# motorController.net
KiCad netlist of a schematic drawn in EAGLE
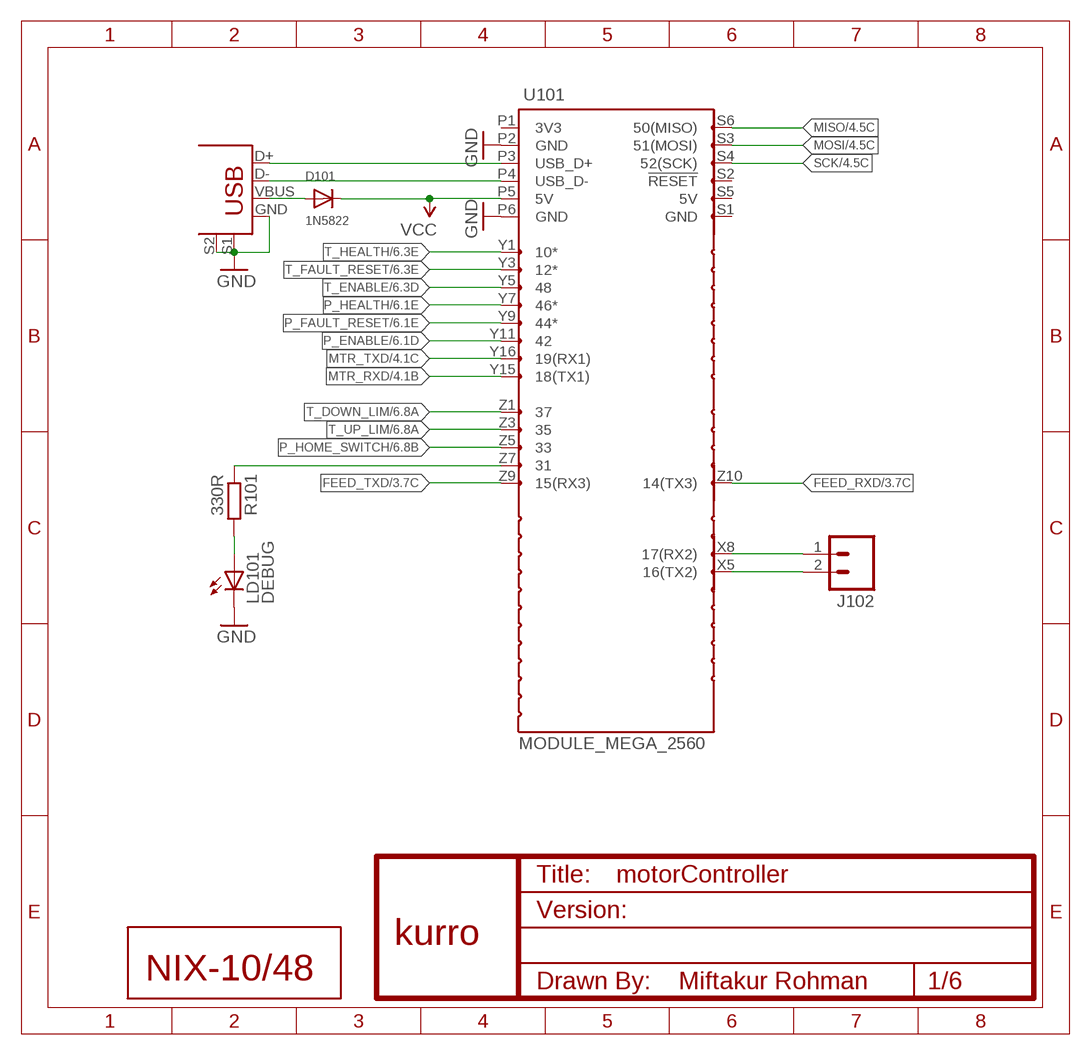
[diagram p0: schematic, sheet 1]
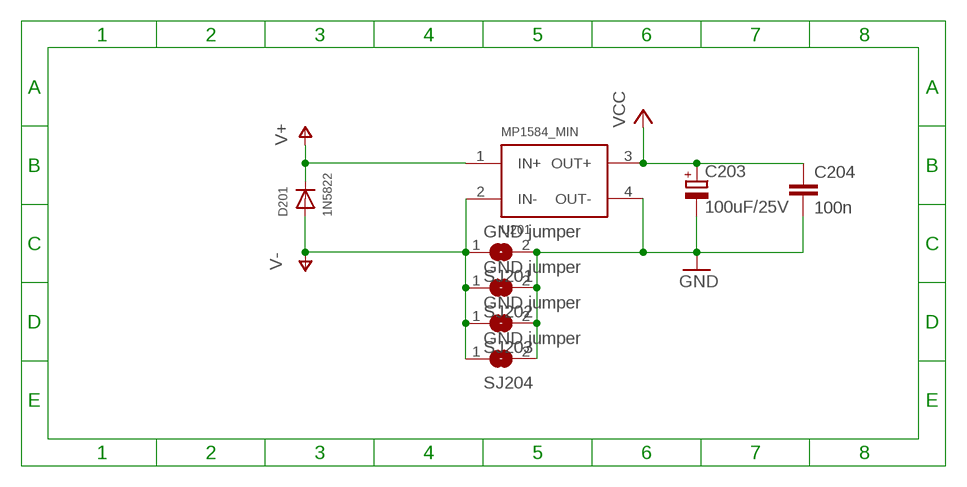
[diagram p1: schematic, sheet 2]
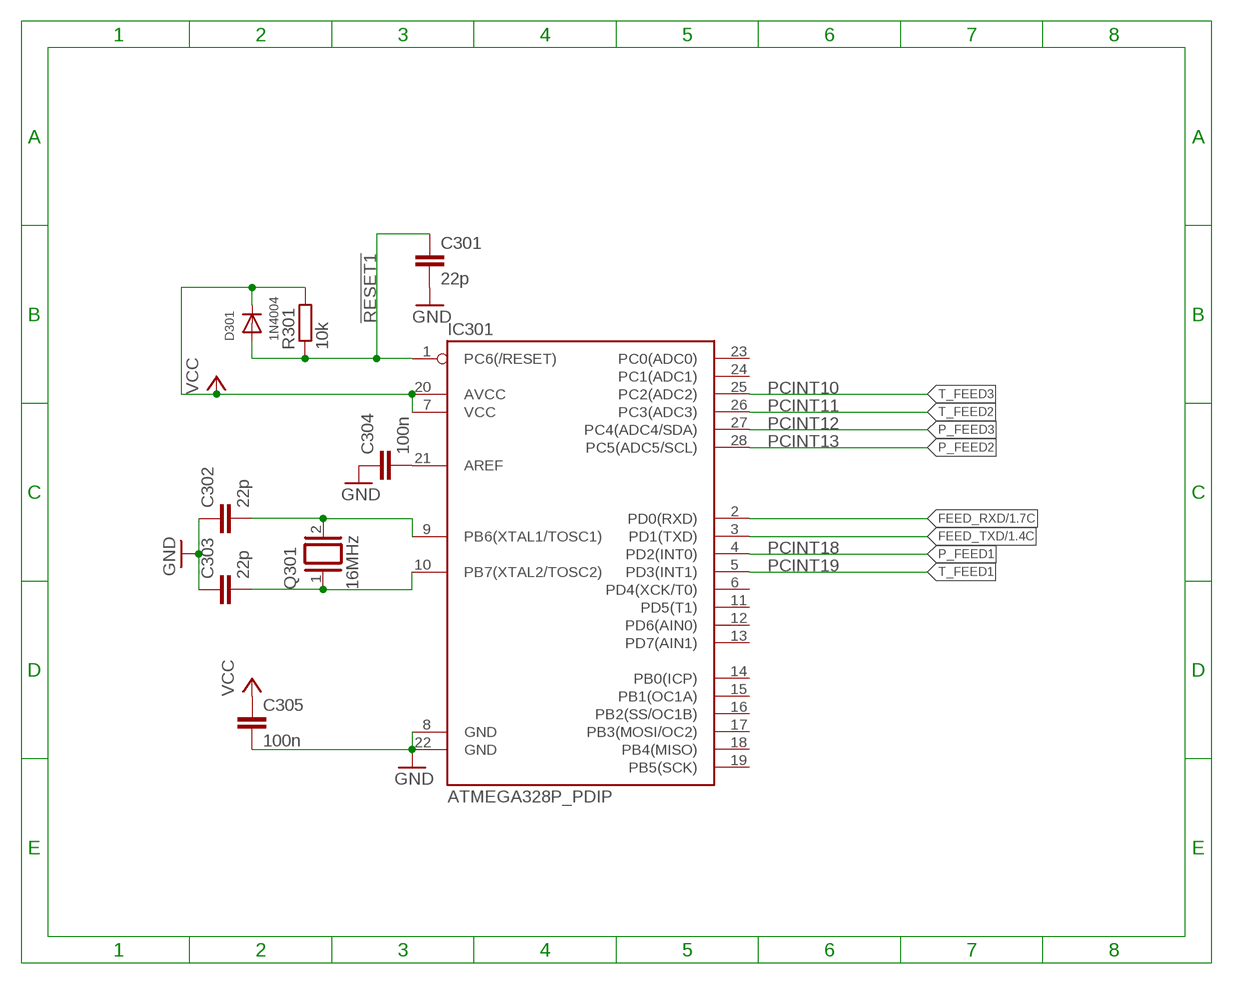
[diagram p2: schematic, sheet 3]
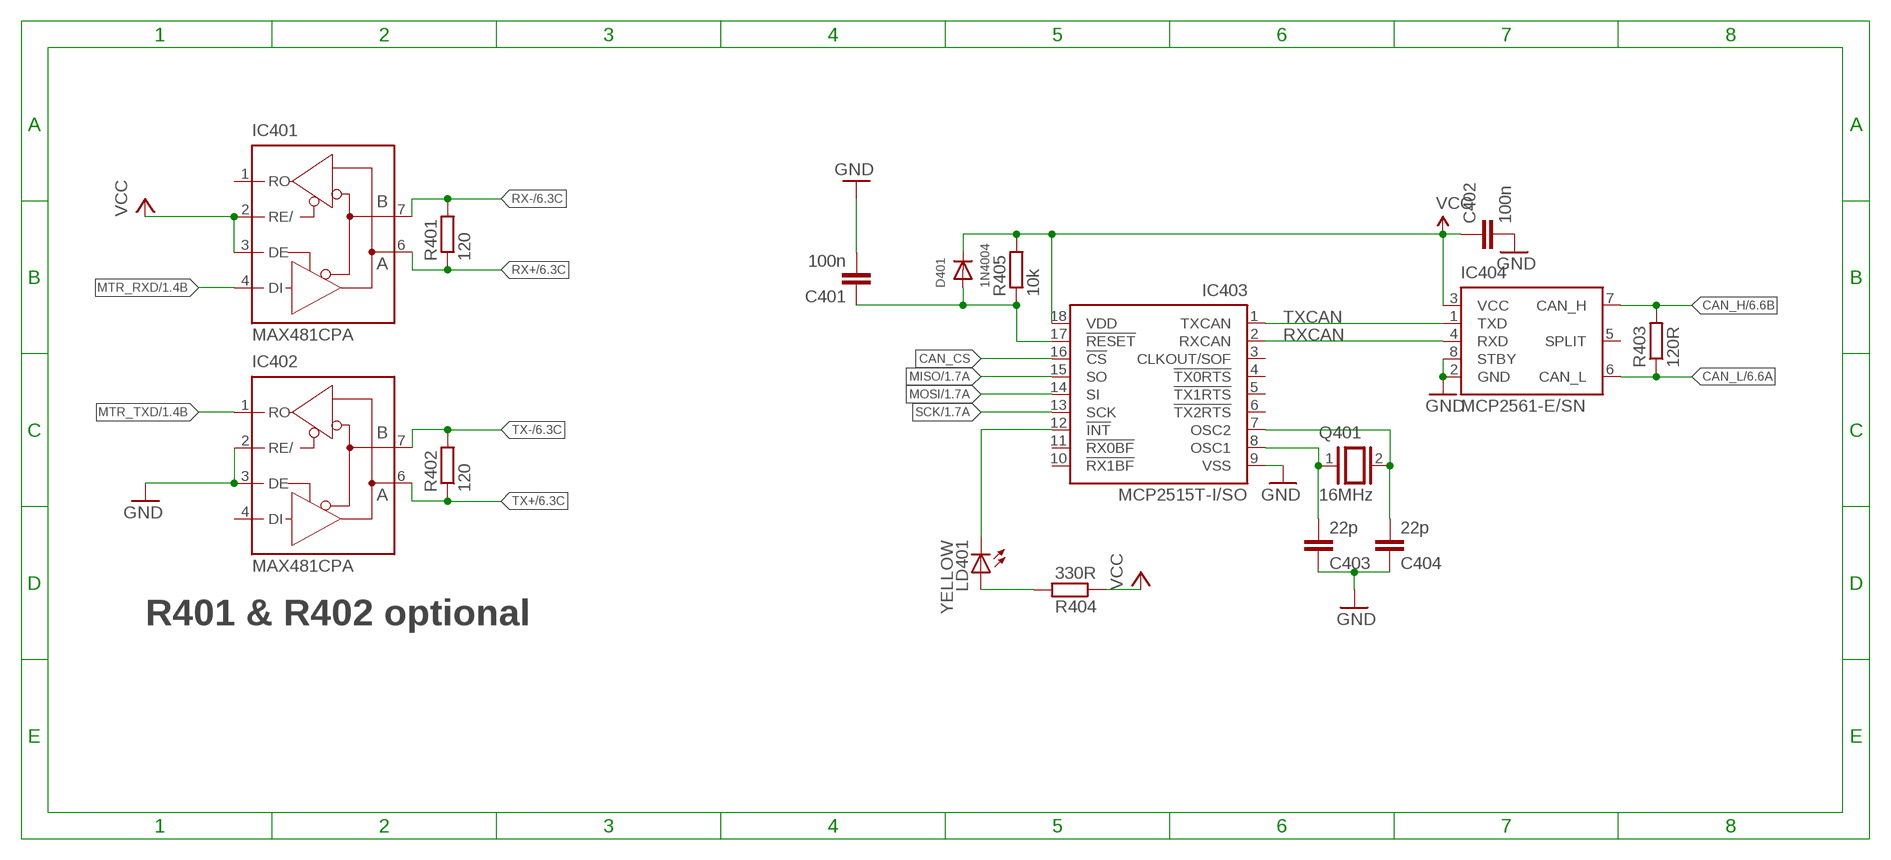
[diagram p3: schematic, sheet 4]
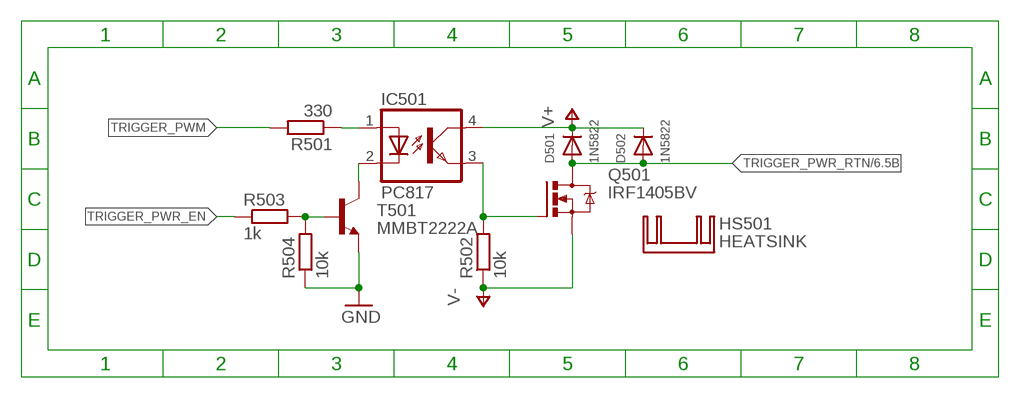
[diagram p4: schematic, sheet 5]
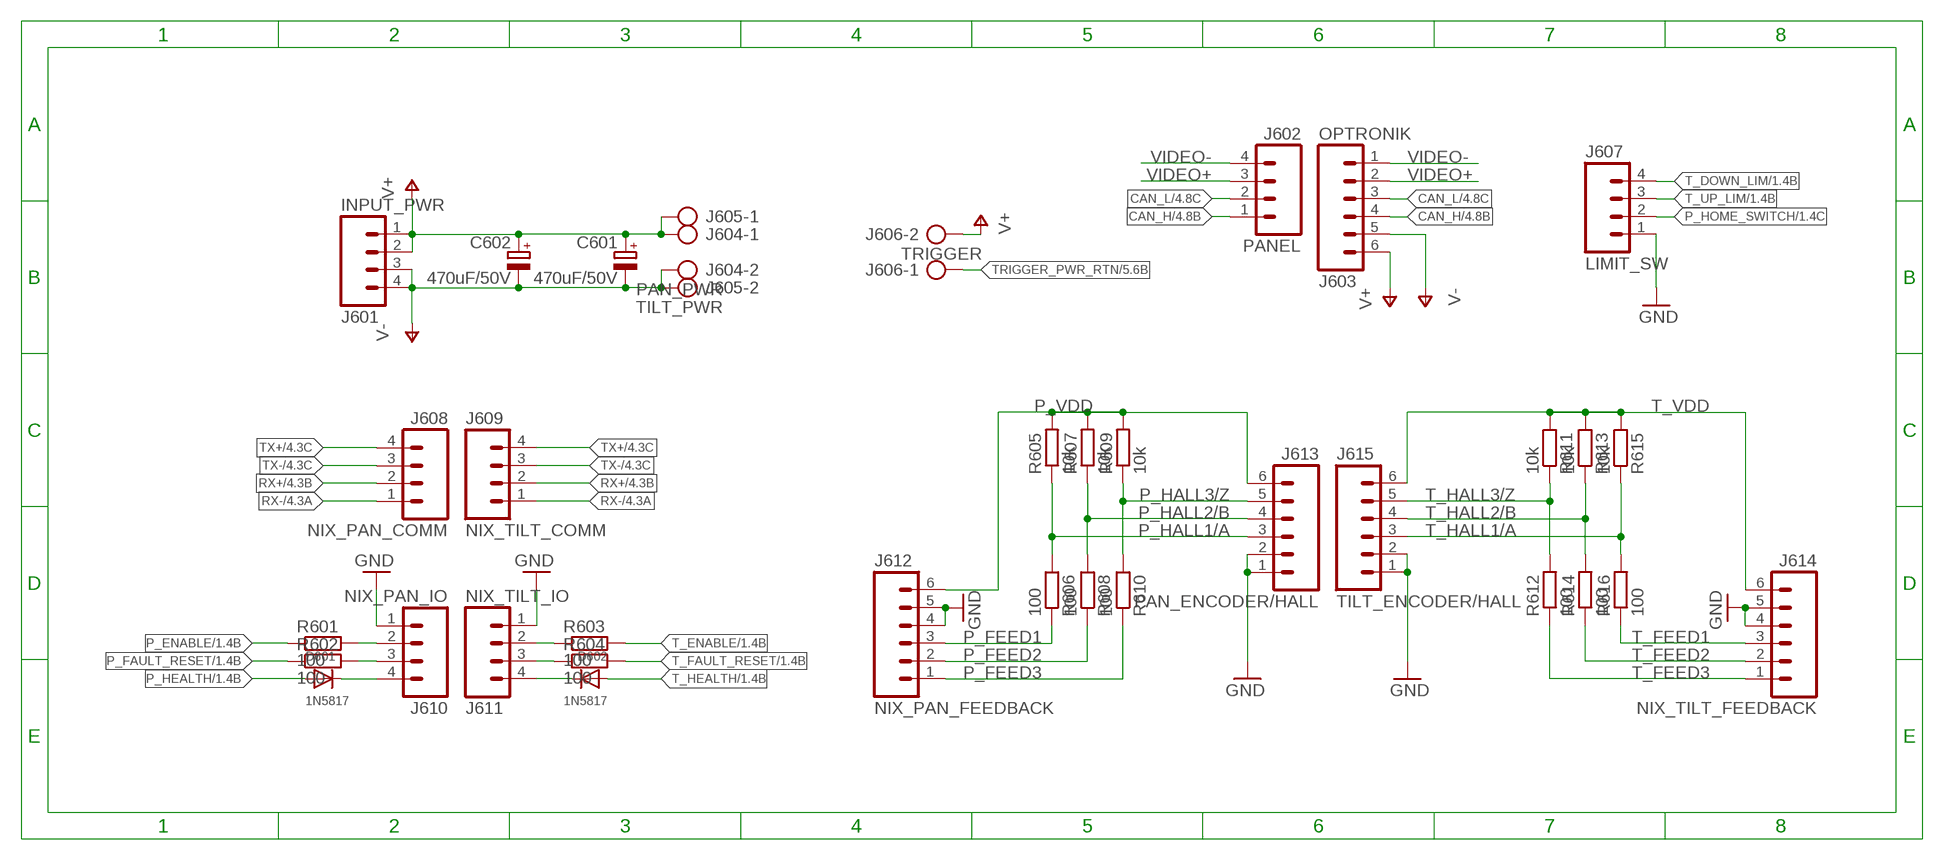
[diagram p5: schematic, sheet 6]

(export (version "E")
  (design (tool "Eeschema 10.0.6"))
  (components
    (comp (ref "D501")
      (value "1N5822")
      (footprint "eagle-import:SMADIODE")
      (libsource (lib "eagle-import") (part "DIODESMA"))
    )
    (comp (ref "D502")
      (value "1N5822")
      (footprint "eagle-import:SMADIODE")
      (libsource (lib "eagle-import") (part "DIODESMA"))
    )
    (comp (ref "HS501")
      (value "HEATSINK")
      (footprint "eagle-import:BV_150X105")
      (libsource (lib "eagle-import") (part "TO220T30"))
    )
    (comp (ref "IC501")
      (value "PC817")
      (footprint "eagle-import:DIL04")
      (libsource (lib "eagle-import") (part "PC817"))
    )
    (comp (ref "Q501")
      (value "IRF1405BV")
      (footprint "eagle-import:TO220BV")
      (libsource (lib "eagle-import") (part "IRF1405BV"))
    )
    (comp (ref "R501")
      (value "330")
      (footprint "eagle-import:R0603")
      (libsource (lib "eagle-import") (part "resistor_R-EU_R0603"))
    )
    (comp (ref "R502")
      (value "10k")
      (footprint "eagle-import:R0603")
      (libsource (lib "eagle-import") (part "resistor_R-EU_R0603"))
    )
    (comp (ref "R503")
      (value "1k")
      (footprint "eagle-import:R0603")
      (libsource (lib "eagle-import") (part "resistor_R-EU_R0603"))
    )
    (comp (ref "R504")
      (value "10k")
      (footprint "eagle-import:R0603")
      (libsource (lib "eagle-import") (part "resistor_R-EU_R0603"))
    )
    (comp (ref "T501")
      (value "MMBT2222A")
      (footprint "eagle-import:SOT23")
      (libsource (lib "eagle-import") (part "TRANSISTOR_NPNSOT23"))
    )
    (comp (ref "C203")
      (value "100uF/25V")
      (footprint "eagle-import:E5-10,5")
      (libsource (lib "eagle-import") (part "CPOL-EUE5-10.5"))
    )
    (comp (ref "C204")
      (value "100n")
      (footprint "eagle-import:C0603")
      (libsource (lib "eagle-import") (part "resistor_C-EUC0603"))
    )
    (comp (ref "D201")
      (value "1N5822")
      (footprint "eagle-import:SMADIODE")
      (libsource (lib "eagle-import") (part "DIODESMA"))
    )
    (comp (ref "SJ201")
      (value "GND jumper")
      (footprint "eagle-import:SJS")
      (libsource (lib "eagle-import") (part "SJS"))
    )
    (comp (ref "SJ202")
      (value "GND jumper")
      (footprint "eagle-import:SJS")
      (libsource (lib "eagle-import") (part "SJS"))
    )
    (comp (ref "SJ203")
      (value "GND jumper")
      (footprint "eagle-import:SJS")
      (libsource (lib "eagle-import") (part "SJS"))
    )
    (comp (ref "SJ204")
      (value "GND jumper")
      (footprint "eagle-import:SJS")
      (libsource (lib "eagle-import") (part "SJS"))
    )
    (comp (ref "U201")
      (value "MP1584_MIN")
      (footprint "eagle-import:MP1584_MIN")
      (libsource (lib "eagle-import") (part "MP1584_MIN"))
    )
    (comp (ref "C601")
      (value "470uF/50V")
      (footprint "eagle-import:E5-10,5")
      (libsource (lib "eagle-import") (part "CPOL-EUE5-10.5"))
    )
    (comp (ref "C602")
      (value "470uF/50V")
      (footprint "eagle-import:E5-10,5")
      (libsource (lib "eagle-import") (part "CPOL-EUE5-10.5"))
    )
    (comp (ref "D601")
      (value "1N5817")
      (footprint "eagle-import:SOD-323F")
      (libsource (lib "eagle-import") (part "DIODESOD-323F"))
    )
    (comp (ref "D602")
      (value "1N5817")
      (footprint "eagle-import:SOD-323F")
      (libsource (lib "eagle-import") (part "DIODESOD-323F"))
    )
    (comp (ref "J601")
      (value "INPUT_PWR")
      (footprint "eagle-import:XH-4-RA")
      (libsource (lib "eagle-import") (part "M04-XH-RA"))
    )
    (comp (ref "J602")
      (value "PANEL")
      (footprint "eagle-import:XH-4-RA")
      (libsource (lib "eagle-import") (part "M04-XH-RA"))
    )
    (comp (ref "J603")
      (value "OPTRONIK")
      (footprint "eagle-import:XH-6-RA")
      (libsource (lib "eagle-import") (part "M06-XH-RA"))
    )
    (comp (ref "J604")
      (value "PAN_PWR")
      (footprint "eagle-import:AK200_2")
      (libsource (lib "eagle-import") (part "AK200/2"))
    )
    (comp (ref "J605")
      (value "TILT_PWR")
      (footprint "eagle-import:AK200_2")
      (libsource (lib "eagle-import") (part "AK200/2"))
    )
    (comp (ref "J606")
      (value "TRIGGER")
      (footprint "eagle-import:AK200_2")
      (libsource (lib "eagle-import") (part "AK200/2"))
    )
    (comp (ref "J607")
      (value "LIMIT_SW")
      (footprint "eagle-import:XH-4-RA")
      (libsource (lib "eagle-import") (part "M04-XH-RA"))
    )
    (comp (ref "J608")
      (value "NIX_PAN_COMM")
      (footprint "eagle-import:XH-4-RA")
      (libsource (lib "eagle-import") (part "M04-XH-RA"))
    )
    (comp (ref "J609")
      (value "NIX_TILT_COMM")
      (footprint "eagle-import:XH-4-RA")
      (libsource (lib "eagle-import") (part "M04-XH-RA"))
    )
    (comp (ref "J610")
      (value "NIX_PAN_IO")
      (footprint "eagle-import:XH-4-RA")
      (libsource (lib "eagle-import") (part "M04-XH-RA"))
    )
    (comp (ref "J611")
      (value "NIX_TILT_IO")
      (footprint "eagle-import:XH-4-RA")
      (libsource (lib "eagle-import") (part "M04-XH-RA"))
    )
    (comp (ref "J612")
      (value "NIX_PAN_FEEDBACK")
      (footprint "eagle-import:XH-6-RA")
      (libsource (lib "eagle-import") (part "M06-XH-RA"))
    )
    (comp (ref "J613")
      (value "PAN_ENCODER/HALL")
      (footprint "eagle-import:MOLEX-1X6")
      (libsource (lib "eagle-import") (part "M06POLAR"))
    )
    (comp (ref "J614")
      (value "NIX_TILT_FEEDBACK")
      (footprint "eagle-import:XH-6-RA")
      (libsource (lib "eagle-import") (part "M06-XH-RA"))
    )
    (comp (ref "J615")
      (value "TILT_ENCODER/HALL")
      (footprint "eagle-import:MOLEX-1X6")
      (libsource (lib "eagle-import") (part "M06POLAR"))
    )
    (comp (ref "R601")
      (value "100")
      (footprint "eagle-import:R0603")
      (libsource (lib "eagle-import") (part "R-EU_R0603"))
    )
    (comp (ref "R602")
      (value "100")
      (footprint "eagle-import:R0603")
      (libsource (lib "eagle-import") (part "R-EU_R0603"))
    )
    (comp (ref "R603")
      (value "100")
      (footprint "eagle-import:R0603")
      (libsource (lib "eagle-import") (part "R-EU_R0603"))
    )
    (comp (ref "R604")
      (value "100")
      (footprint "eagle-import:R0603")
      (libsource (lib "eagle-import") (part "R-EU_R0603"))
    )
    (comp (ref "R605")
      (value "10k")
      (footprint "eagle-import:R0603")
      (libsource (lib "eagle-import") (part "R-EU_R0603"))
    )
    (comp (ref "R606")
      (value "100")
      (footprint "eagle-import:R0603")
      (libsource (lib "eagle-import") (part "R-EU_R0603"))
    )
    (comp (ref "R607")
      (value "10k")
      (footprint "eagle-import:R0603")
      (libsource (lib "eagle-import") (part "R-EU_R0603"))
    )
    (comp (ref "R608")
      (value "100")
      (footprint "eagle-import:R0603")
      (libsource (lib "eagle-import") (part "R-EU_R0603"))
    )
    (comp (ref "R609")
      (value "10k")
      (footprint "eagle-import:R0603")
      (libsource (lib "eagle-import") (part "R-EU_R0603"))
    )
    (comp (ref "R610")
      (value "100")
      (footprint "eagle-import:R0603")
      (libsource (lib "eagle-import") (part "R-EU_R0603"))
    )
    (comp (ref "R611")
      (value "10k")
      (footprint "eagle-import:R0603")
      (libsource (lib "eagle-import") (part "R-EU_R0603"))
    )
    (comp (ref "R612")
      (value "100")
      (footprint "eagle-import:R0603")
      (libsource (lib "eagle-import") (part "R-EU_R0603"))
    )
    (comp (ref "R613")
      (value "10k")
      (footprint "eagle-import:R0603")
      (libsource (lib "eagle-import") (part "R-EU_R0603"))
    )
    (comp (ref "R614")
      (value "100")
      (footprint "eagle-import:R0603")
      (libsource (lib "eagle-import") (part "R-EU_R0603"))
    )
    (comp (ref "R615")
      (value "10k")
      (footprint "eagle-import:R0603")
      (libsource (lib "eagle-import") (part "R-EU_R0603"))
    )
    (comp (ref "R616")
      (value "100")
      (footprint "eagle-import:R0603")
      (libsource (lib "eagle-import") (part "R-EU_R0603"))
    )
    (comp (ref "C401")
      (value "100n")
      (footprint "eagle-import:C0603")
      (libsource (lib "eagle-import") (part "C-EUC0603"))
    )
    (comp (ref "C402")
      (value "100n")
      (footprint "eagle-import:C0603")
      (libsource (lib "eagle-import") (part "C-EUC0603"))
    )
    (comp (ref "C403")
      (value "22p")
      (footprint "eagle-import:C0603")
      (libsource (lib "eagle-import") (part "C-EUC0603"))
    )
    (comp (ref "C404")
      (value "22p")
      (footprint "eagle-import:C0603")
      (libsource (lib "eagle-import") (part "C-EUC0603"))
    )
    (comp (ref "D401")
      (value "1N4004")
      (footprint "eagle-import:SOD-323F")
      (libsource (lib "eagle-import") (part "DIODESOD-323F"))
    )
    (comp (ref "IC401")
      (value "MAX481CPA")
      (footprint "eagle-import:DIL08")
      (libsource (lib "eagle-import") (part "MAX481CPA"))
    )
    (comp (ref "IC402")
      (value "MAX481CPA")
      (footprint "eagle-import:DIL08")
      (libsource (lib "eagle-import") (part "MAX481CPA"))
    )
    (comp (ref "IC403")
      (value "MCP2515T-I/SO")
      (footprint "eagle-import:SO-18")
      (libsource (lib "eagle-import") (part "MCP2515T-I/SO"))
    )
    (comp (ref "IC404")
      (value "MCP2561-E/SN")
      (footprint "eagle-import:SOIC-8")
      (libsource (lib "eagle-import") (part "MCP2561-E/SN"))
    )
    (comp (ref "LD401")
      (value "YELLOW")
      (footprint "eagle-import:LED5MM")
      (libsource (lib "eagle-import") (part "led_LED5MM"))
    )
    (comp (ref "Q401")
      (value "16MHz")
      (footprint "eagle-import:QS")
      (libsource (lib "eagle-import") (part "XTAL/S"))
    )
    (comp (ref "R401")
      (value "120")
      (footprint "eagle-import:R0603")
      (libsource (lib "eagle-import") (part "R-EU_R0603"))
    )
    (comp (ref "R402")
      (value "120")
      (footprint "eagle-import:R0603")
      (libsource (lib "eagle-import") (part "R-EU_R0603"))
    )
    (comp (ref "R403")
      (value "120R")
      (footprint "eagle-import:R0603")
      (libsource (lib "eagle-import") (part "R-EU_R0603"))
    )
    (comp (ref "R404")
      (value "330R")
      (footprint "eagle-import:R0603")
      (libsource (lib "eagle-import") (part "resistor_R-EU_R0603"))
    )
    (comp (ref "R405")
      (value "10k")
      (footprint "eagle-import:R0603")
      (libsource (lib "eagle-import") (part "R-EU_R0603"))
    )
    (comp (ref "C301")
      (value "22p")
      (footprint "eagle-import:C0603")
      (libsource (lib "eagle-import") (part "resistor_C-EUC0603"))
    )
    (comp (ref "C302")
      (value "22p")
      (footprint "eagle-import:C0603")
      (libsource (lib "eagle-import") (part "C-EUC0603"))
    )
    (comp (ref "C303")
      (value "22p")
      (footprint "eagle-import:C0603")
      (libsource (lib "eagle-import") (part "C-EUC0603"))
    )
    (comp (ref "C304")
      (value "100n")
      (footprint "eagle-import:C0603")
      (libsource (lib "eagle-import") (part "resistor_C-EUC0603"))
    )
    (comp (ref "C305")
      (value "100n")
      (footprint "eagle-import:C0603")
      (libsource (lib "eagle-import") (part "resistor_C-EUC0603"))
    )
    (comp (ref "D301")
      (value "1N4004")
      (footprint "eagle-import:SOD-323F")
      (libsource (lib "eagle-import") (part "DIODESOD-323F"))
    )
    (comp (ref "IC301")
      (value "ATMEGA328P_PDIP")
      (footprint "eagle-import:DIL28-3")
      (libsource (lib "eagle-import") (part "ATMEGA328P_PDIP"))
    )
    (comp (ref "Q301")
      (value "16MHz")
      (footprint "eagle-import:QS")
      (libsource (lib "eagle-import") (part "XTAL/S"))
    )
    (comp (ref "R301")
      (value "10k")
      (footprint "eagle-import:R0603")
      (libsource (lib "eagle-import") (part "R-EU_R0603"))
    )
    (comp (ref "D101")
      (value "1N5822")
      (footprint "eagle-import:SMADIODE")
      (libsource (lib "eagle-import") (part "DIODESMA"))
    )
    (comp (ref "J101")
      (value "USB+SHIELD")
      (footprint "eagle-import:USB-B-PTH")
      (libsource (lib "eagle-import") (part "USB+SHIELD"))
    )
    (comp (ref "J102")
      (value "M02POLAR")
      (footprint "eagle-import:MOLEX-1X2")
      (libsource (lib "eagle-import") (part "M02POLAR"))
    )
    (comp (ref "LD101")
      (value "DEBUG")
      (footprint "eagle-import:LED5MM")
      (libsource (lib "eagle-import") (part "LED5MM"))
    )
    (comp (ref "R101")
      (value "330R")
      (footprint "eagle-import:R0603")
      (libsource (lib "eagle-import") (part "resistor_R-EU_R0603"))
    )
    (comp (ref "U$1")
      (value "KURRO_FOOTPRINT")
      (footprint "eagle-import:KURRO-LOGO")
      (libsource (lib "eagle-import") (part "KURRO_FOOTPRINT"))
    )
    (comp (ref "U$2")
      (value "NIX")
      (footprint "eagle-import:NIX-XX_XXX")
      (libsource (lib "eagle-import") (part "NIX"))
    )
    (comp (ref "U$3")
      (value "MOD_MEGA_LAYOUT_ICSP")
      (footprint "eagle-import:MOD_MEGA_LAYOUT_ICSP")
      (libsource (lib "eagle-import") (part "MOD_MEGA_LAYOUT_ICSP"))
    )
    (comp (ref "U$4")
      (value "MOD_MEGA_LAYOUT_SERIAL1")
      (footprint "eagle-import:MOD_MEGA_LAYOUT_SERIAL1")
      (libsource (lib "eagle-import") (part "MOD_MEGA_LAYOUT_SERIAL1"))
    )
    (comp (ref "U$5")
      (value "MOD_MEGA_LAYOUT_SERIAL2")
      (footprint "eagle-import:MOD_MEGA_LAYOUT_SERIAL2")
      (libsource (lib "eagle-import") (part "MOD_MEGA_LAYOUT_SERIAL2"))
    )
    (comp (ref "U$6")
      (value "MOD_MEGA_LAYOUT_SERIAL3")
      (footprint "eagle-import:MOD_MEGA_LAYOUT_SERIAL3")
      (libsource (lib "eagle-import") (part "MOD_MEGA_LAYOUT_SERIAL3"))
    )
    (comp (ref "U$7")
      (value "MOD_MEGA_LAYOUT_Z_ODD")
      (footprint "eagle-import:MOD_MEGA_LAYOUT_Z_ODD")
      (libsource (lib "eagle-import") (part "MOD_MEGA_LAYOUT_Z_ODD"))
    )
    (comp (ref "U$9")
      (value "MOD_MEGA_LAYOUT_Y_ODD")
      (footprint "eagle-import:MOD_MEGA_LAYOUT_Y_ODD")
      (libsource (lib "eagle-import") (part "MOD_MEGA_LAYOUT_Y_ODD"))
    )
    (comp (ref "U101")
      (value "MODULE_MEGA_2560")
      (footprint "eagle-import:MOD_MEGA_LAYOUT")
      (libsource (lib "eagle-import") (part "MOD_MEGA_LAYOUT"))
    )
  )
  (nets
    (net (code "1") (name "CAN_CS") (class "Default")
      (node (ref "IC403") (pin "16") (pinfunction "~{CS}_16") (pintype "bidirectional"))
    )
    (net (code "2") (name "CAN_H") (class "Default")
      (node (ref "IC404") (pin "7") (pinfunction "CAN_H_7") (pintype "bidirectional"))
      (node (ref "J602") (pin "1") (pinfunction "1_1") (pintype "passive"))
      (node (ref "J603") (pin "4") (pinfunction "4_4") (pintype "passive"))
      (node (ref "R403") (pin "2") (pinfunction "2_2") (pintype "passive"))
    )
    (net (code "3") (name "CAN_L") (class "Default")
      (node (ref "IC404") (pin "6") (pinfunction "CAN_L_6") (pintype "bidirectional"))
      (node (ref "J602") (pin "2") (pinfunction "2_2") (pintype "passive"))
      (node (ref "J603") (pin "3") (pinfunction "3_3") (pintype "passive"))
      (node (ref "R403") (pin "1") (pinfunction "1_1") (pintype "passive"))
    )
    (net (code "4") (name "FEED_RXD") (class "Default")
      (node (ref "IC301") (pin "2") (pinfunction "PD0(RXD)_2") (pintype "bidirectional"))
      (node (ref "U$6") (pin "Z10") (pinfunction "14(TX3)_Z10") (pintype "bidirectional"))
    )
    (net (code "5") (name "FEED_TXD") (class "Default")
      (node (ref "IC301") (pin "3") (pinfunction "PD1(TXD)_3") (pintype "bidirectional"))
      (node (ref "U$6") (pin "Z9") (pinfunction "15(RX3)_Z9") (pintype "bidirectional"))
    )
    (net (code "6") (name "GND") (class "Default")
      (node (ref "C203") (pin "-") (pinfunction "-_-") (pintype "passive"))
      (node (ref "C204") (pin "2") (pinfunction "2_2") (pintype "passive"))
      (node (ref "C301") (pin "2") (pinfunction "2_2") (pintype "passive"))
      (node (ref "C302") (pin "1") (pinfunction "1_1") (pintype "passive"))
      (node (ref "C303") (pin "1") (pinfunction "1_1") (pintype "passive"))
      (node (ref "C304") (pin "1") (pinfunction "1_1") (pintype "passive"))
      (node (ref "C305") (pin "2") (pinfunction "2_2") (pintype "passive"))
      (node (ref "C401") (pin "2") (pinfunction "2_2") (pintype "passive"))
      (node (ref "C402") (pin "2") (pinfunction "2_2") (pintype "passive"))
      (node (ref "C403") (pin "1") (pinfunction "1_1") (pintype "passive"))
      (node (ref "C404") (pin "1") (pinfunction "1_1") (pintype "passive"))
      (node (ref "IC301") (pin "22") (pinfunction "GND_22") (pintype "bidirectional"))
      (node (ref "IC301") (pin "8") (pinfunction "GND_8") (pintype "bidirectional"))
      (node (ref "IC402") (pin "2") (pinfunction "RE/_2") (pintype "input"))
      (node (ref "IC402") (pin "3") (pinfunction "DE_3") (pintype "input"))
      (node (ref "IC403") (pin "9") (pinfunction "VSS_9") (pintype "bidirectional"))
      (node (ref "IC404") (pin "2") (pinfunction "GND_2") (pintype "bidirectional"))
      (node (ref "IC404") (pin "8") (pinfunction "STBY_8") (pintype "bidirectional"))
      (node (ref "J101") (pin "GND") (pinfunction "GND_GND") (pintype "bidirectional"))
      (node (ref "J101") (pin "S1") (pinfunction "S1_S1") (pintype "bidirectional"))
      (node (ref "J101") (pin "S2") (pinfunction "S2_S2") (pintype "bidirectional"))
      (node (ref "J607") (pin "1") (pinfunction "1_1") (pintype "passive"))
      (node (ref "J610") (pin "1") (pinfunction "1_1") (pintype "passive"))
      (node (ref "J611") (pin "1") (pinfunction "1_1") (pintype "passive"))
      (node (ref "J612") (pin "4") (pinfunction "4_4") (pintype "passive"))
      (node (ref "J612") (pin "5") (pinfunction "5_5") (pintype "passive"))
      (node (ref "J613") (pin "1") (pinfunction "1_1") (pintype "passive"))
      (node (ref "J613") (pin "2") (pinfunction "2_2") (pintype "passive"))
      (node (ref "J614") (pin "4") (pinfunction "4_4") (pintype "passive"))
      (node (ref "J614") (pin "5") (pinfunction "5_5") (pintype "passive"))
      (node (ref "J615") (pin "1") (pinfunction "1_1") (pintype "passive"))
      (node (ref "J615") (pin "2") (pinfunction "2_2") (pintype "passive"))
      (node (ref "LD101") (pin "K") (pinfunction "C_K") (pintype "passive"))
      (node (ref "R504") (pin "1") (pinfunction "1_1") (pintype "passive"))
      (node (ref "SJ201") (pin "2") (pinfunction "2_2") (pintype "passive"))
      (node (ref "SJ202") (pin "2") (pinfunction "2_2") (pintype "passive"))
      (node (ref "SJ203") (pin "2") (pinfunction "2_2") (pintype "passive"))
      (node (ref "SJ204") (pin "2") (pinfunction "2_2") (pintype "passive"))
      (node (ref "T501") (pin "2") (pinfunction "E_2") (pintype "passive"))
      (node (ref "U101") (pin "P2") (pinfunction "GND_P2") (pintype "bidirectional"))
      (node (ref "U101") (pin "P6") (pinfunction "GND_P6") (pintype "bidirectional"))
      (node (ref "U201") (pin "4") (pinfunction "OUT-_4") (pintype "passive"))
    )
    (net (code "7") (name "MISO") (class "Default")
      (node (ref "IC403") (pin "15") (pinfunction "SO_15") (pintype "bidirectional"))
      (node (ref "U$3") (pin "S6") (pinfunction "50(MISO)_S6") (pintype "bidirectional"))
    )
    (net (code "8") (name "MOSI") (class "Default")
      (node (ref "IC403") (pin "14") (pinfunction "SI_14") (pintype "bidirectional"))
      (node (ref "U$3") (pin "S3") (pinfunction "51(MOSI)_S3") (pintype "bidirectional"))
    )
    (net (code "9") (name "MTR_RXD") (class "Default")
      (node (ref "IC401") (pin "4") (pinfunction "DI_4") (pintype "input"))
      (node (ref "U$4") (pin "Y15") (pinfunction "18(TX1)_Y15") (pintype "bidirectional"))
    )
    (net (code "10") (name "MTR_TXD") (class "Default")
      (node (ref "IC402") (pin "1") (pinfunction "RO_1") (pintype "output"))
      (node (ref "U$4") (pin "Y16") (pinfunction "19(RX1)_Y16") (pintype "bidirectional"))
    )
    (net (code "11") (name "Net-(D101-PadA)") (class "Default")
      (node (ref "D101") (pin "A") (pinfunction "A_A") (pintype "passive"))
      (node (ref "J101") (pin "VBUS") (pinfunction "VBUS_VBUS") (pintype "bidirectional"))
    )
    (net (code "12") (name "Net-(D601-PadC)") (class "Default")
      (node (ref "D601") (pin "C") (pinfunction "C_C") (pintype "passive"))
      (node (ref "J610") (pin "4") (pinfunction "4_4") (pintype "passive"))
    )
    (net (code "13") (name "Net-(D602-PadC)") (class "Default")
      (node (ref "D602") (pin "C") (pinfunction "C_C") (pintype "passive"))
      (node (ref "J611") (pin "4") (pinfunction "4_4") (pintype "passive"))
    )
    (net (code "14") (name "Net-(IC301-AREF)") (class "Default")
      (node (ref "C304") (pin "2") (pinfunction "2_2") (pintype "passive"))
      (node (ref "IC301") (pin "21") (pinfunction "AREF_21") (pintype "bidirectional"))
    )
    (net (code "15") (name "Net-(IC301-PB6(XTAL1{slash}TOSC1))") (class "Default")
      (node (ref "C302") (pin "2") (pinfunction "2_2") (pintype "passive"))
      (node (ref "IC301") (pin "9") (pinfunction "PB6(XTAL1/TOSC1)_9") (pintype "bidirectional"))
      (node (ref "Q301") (pin "2") (pinfunction "2_2") (pintype "passive"))
    )
    (net (code "16") (name "Net-(IC301-PB7(XTAL2{slash}TOSC2))") (class "Default")
      (node (ref "C303") (pin "2") (pinfunction "2_2") (pintype "passive"))
      (node (ref "IC301") (pin "10") (pinfunction "PB7(XTAL2/TOSC2)_10") (pintype "bidirectional"))
      (node (ref "Q301") (pin "1") (pinfunction "1_1") (pintype "passive"))
    )
    (net (code "17") (name "Net-(IC403-OSC1)") (class "Default")
      (node (ref "C403") (pin "2") (pinfunction "2_2") (pintype "passive"))
      (node (ref "IC403") (pin "8") (pinfunction "OSC1_8") (pintype "bidirectional"))
      (node (ref "Q401") (pin "1") (pinfunction "1_1") (pintype "passive"))
    )
    (net (code "18") (name "Net-(IC403-OSC2)") (class "Default")
      (node (ref "C404") (pin "2") (pinfunction "2_2") (pintype "passive"))
      (node (ref "IC403") (pin "7") (pinfunction "OSC2_7") (pintype "bidirectional"))
      (node (ref "Q401") (pin "2") (pinfunction "2_2") (pintype "passive"))
    )
    (net (code "19") (name "Net-(IC403-~{INT})") (class "Default")
      (node (ref "IC403") (pin "12") (pinfunction "~{INT}_12") (pintype "bidirectional"))
      (node (ref "LD401") (pin "K") (pinfunction "C_K") (pintype "passive"))
    )
    (net (code "20") (name "Net-(IC403-~{RESET})") (class "Default")
      (node (ref "C401") (pin "1") (pinfunction "1_1") (pintype "passive"))
      (node (ref "D401") (pin "A") (pinfunction "A_A") (pintype "passive"))
      (node (ref "IC403") (pin "17") (pinfunction "~{RESET}_17") (pintype "bidirectional"))
      (node (ref "R405") (pin "1") (pinfunction "1_1") (pintype "passive"))
    )
    (net (code "21") (name "Net-(IC501-A)") (class "Default")
      (node (ref "IC501") (pin "1") (pinfunction "A_1") (pintype "passive"))
      (node (ref "R501") (pin "1") (pinfunction "1_1") (pintype "passive"))
    )
    (net (code "22") (name "Net-(IC501-C)") (class "Default")
      (node (ref "IC501") (pin "2") (pinfunction "C_2") (pintype "passive"))
      (node (ref "T501") (pin "3") (pinfunction "C_3") (pintype "passive"))
    )
    (net (code "23") (name "Net-(IC501-EMIT)") (class "Default")
      (node (ref "IC501") (pin "3") (pinfunction "EMIT_3") (pintype "passive"))
      (node (ref "Q501") (pin "G") (pinfunction "G_G") (pintype "passive"))
      (node (ref "R502") (pin "2") (pinfunction "2_2") (pintype "passive"))
    )
    (net (code "24") (name "Net-(J610-Pad2)") (class "Default")
      (node (ref "J610") (pin "2") (pinfunction "2_2") (pintype "passive"))
      (node (ref "R601") (pin "2") (pinfunction "2_2") (pintype "passive"))
    )
    (net (code "25") (name "Net-(J610-Pad3)") (class "Default")
      (node (ref "J610") (pin "3") (pinfunction "3_3") (pintype "passive"))
      (node (ref "R602") (pin "2") (pinfunction "2_2") (pintype "passive"))
    )
    (net (code "26") (name "Net-(J611-Pad2)") (class "Default")
      (node (ref "J611") (pin "2") (pinfunction "2_2") (pintype "passive"))
      (node (ref "R603") (pin "1") (pinfunction "1_1") (pintype "passive"))
    )
    (net (code "27") (name "Net-(J611-Pad3)") (class "Default")
      (node (ref "J611") (pin "3") (pinfunction "3_3") (pintype "passive"))
      (node (ref "R604") (pin "1") (pinfunction "1_1") (pintype "passive"))
    )
    (net (code "28") (name "Net-(LD101-PadA)") (class "Default")
      (node (ref "LD101") (pin "A") (pinfunction "A_A") (pintype "passive"))
      (node (ref "R101") (pin "2") (pinfunction "2_2") (pintype "passive"))
    )
    (net (code "29") (name "Net-(LD401-PadA)") (class "Default")
      (node (ref "LD401") (pin "A") (pinfunction "A_A") (pintype "passive"))
      (node (ref "R404") (pin "2") (pinfunction "2_2") (pintype "passive"))
    )
    (net (code "30") (name "Net-(T501-B)") (class "Default")
      (node (ref "R503") (pin "2") (pinfunction "2_2") (pintype "passive"))
      (node (ref "R504") (pin "2") (pinfunction "2_2") (pintype "passive"))
      (node (ref "T501") (pin "1") (pinfunction "B_1") (pintype "passive"))
    )
    (net (code "31") (name "Net-(U$5-16(TX2))") (class "Default")
      (node (ref "J102") (pin "2") (pinfunction "2_2") (pintype "passive"))
      (node (ref "U$5") (pin "X5") (pinfunction "16(TX2)_X5") (pintype "bidirectional"))
    )
    (net (code "32") (name "Net-(U$5-17(RX2))") (class "Default")
      (node (ref "J102") (pin "1") (pinfunction "1_1") (pintype "passive"))
      (node (ref "U$5") (pin "X8") (pinfunction "17(RX2)_X8") (pintype "bidirectional"))
    )
    (net (code "33") (name "Net-(U$7-31)") (class "Default")
      (node (ref "R101") (pin "1") (pinfunction "1_1") (pintype "passive"))
      (node (ref "U$7") (pin "Z7") (pinfunction "31_Z7") (pintype "bidirectional"))
    )
    (net (code "34") (name "Net-(U101-USB_D+)") (class "Default")
      (node (ref "J101") (pin "D+") (pinfunction "D+_D+") (pintype "bidirectional"))
      (node (ref "U101") (pin "P3") (pinfunction "USB_D+_P3") (pintype "bidirectional"))
    )
    (net (code "35") (name "Net-(U101-USB_D-)") (class "Default")
      (node (ref "J101") (pin "D-") (pinfunction "D-_D-") (pintype "bidirectional"))
      (node (ref "U101") (pin "P4") (pinfunction "USB_D-_P4") (pintype "bidirectional"))
    )
    (net (code "36") (name "P_ENABLE") (class "Default")
      (node (ref "R601") (pin "1") (pinfunction "1_1") (pintype "passive"))
      (node (ref "U$9") (pin "Y11") (pinfunction "42_Y11") (pintype "bidirectional"))
    )
    (net (code "37") (name "P_FAULT_RESET") (class "Default")
      (node (ref "R602") (pin "1") (pinfunction "1_1") (pintype "passive"))
      (node (ref "U$9") (pin "Y9") (pinfunction "44*_Y9") (pintype "bidirectional"))
    )
    (net (code "38") (name "P_FEED1") (class "Default")
      (node (ref "IC301") (pin "4") (pinfunction "PD2(INT0)_4") (pintype "bidirectional"))
      (node (ref "J612") (pin "3") (pinfunction "3_3") (pintype "passive"))
      (node (ref "R606") (pin "1") (pinfunction "1_1") (pintype "passive"))
    )
    (net (code "39") (name "P_FEED2") (class "Default")
      (node (ref "IC301") (pin "28") (pinfunction "PC5(ADC5/SCL)_28") (pintype "bidirectional"))
      (node (ref "J612") (pin "2") (pinfunction "2_2") (pintype "passive"))
      (node (ref "R608") (pin "1") (pinfunction "1_1") (pintype "passive"))
    )
    (net (code "40") (name "P_FEED3") (class "Default")
      (node (ref "IC301") (pin "27") (pinfunction "PC4(ADC4/SDA)_27") (pintype "bidirectional"))
      (node (ref "J612") (pin "1") (pinfunction "1_1") (pintype "passive"))
      (node (ref "R610") (pin "1") (pinfunction "1_1") (pintype "passive"))
    )
    (net (code "41") (name "P_HALL1{slash}A") (class "Default")
      (node (ref "J613") (pin "3") (pinfunction "3_3") (pintype "passive"))
      (node (ref "R605") (pin "1") (pinfunction "1_1") (pintype "passive"))
      (node (ref "R606") (pin "2") (pinfunction "2_2") (pintype "passive"))
    )
    (net (code "42") (name "P_HALL2{slash}B") (class "Default")
      (node (ref "J613") (pin "4") (pinfunction "4_4") (pintype "passive"))
      (node (ref "R607") (pin "1") (pinfunction "1_1") (pintype "passive"))
      (node (ref "R608") (pin "2") (pinfunction "2_2") (pintype "passive"))
    )
    (net (code "43") (name "P_HALL3{slash}Z") (class "Default")
      (node (ref "J613") (pin "5") (pinfunction "5_5") (pintype "passive"))
      (node (ref "R609") (pin "1") (pinfunction "1_1") (pintype "passive"))
      (node (ref "R610") (pin "2") (pinfunction "2_2") (pintype "passive"))
    )
    (net (code "44") (name "P_HEALTH") (class "Default")
      (node (ref "D601") (pin "A") (pinfunction "A_A") (pintype "passive"))
      (node (ref "U$9") (pin "Y7") (pinfunction "46*_Y7") (pintype "bidirectional"))
    )
    (net (code "45") (name "P_HOME_SWITCH") (class "Default")
      (node (ref "J607") (pin "2") (pinfunction "2_2") (pintype "passive"))
      (node (ref "U$7") (pin "Z5") (pinfunction "33_Z5") (pintype "bidirectional"))
    )
    (net (code "46") (name "P_VDD") (class "Default")
      (node (ref "J612") (pin "6") (pinfunction "6_6") (pintype "passive"))
      (node (ref "J613") (pin "6") (pinfunction "6_6") (pintype "passive"))
      (node (ref "R605") (pin "2") (pinfunction "2_2") (pintype "passive"))
      (node (ref "R607") (pin "2") (pinfunction "2_2") (pintype "passive"))
      (node (ref "R609") (pin "2") (pinfunction "2_2") (pintype "passive"))
    )
    (net (code "47") (name "RX+") (class "Default")
      (node (ref "IC401") (pin "6") (pinfunction "A_6") (pintype "passive"))
      (node (ref "J608") (pin "2") (pinfunction "2_2") (pintype "passive"))
      (node (ref "J609") (pin "2") (pinfunction "2_2") (pintype "passive"))
      (node (ref "R401") (pin "1") (pinfunction "1_1") (pintype "passive"))
    )
    (net (code "48") (name "RX-") (class "Default")
      (node (ref "IC401") (pin "7") (pinfunction "B_7") (pintype "passive"))
      (node (ref "J608") (pin "1") (pinfunction "1_1") (pintype "passive"))
      (node (ref "J609") (pin "1") (pinfunction "1_1") (pintype "passive"))
      (node (ref "R401") (pin "2") (pinfunction "2_2") (pintype "passive"))
    )
    (net (code "49") (name "RXCAN") (class "Default")
      (node (ref "IC403") (pin "2") (pinfunction "RXCAN_2") (pintype "bidirectional"))
      (node (ref "IC404") (pin "4") (pinfunction "RXD_4") (pintype "bidirectional"))
    )
    (net (code "50") (name "SCK") (class "Default")
      (node (ref "IC403") (pin "13") (pinfunction "SCK_13") (pintype "bidirectional"))
      (node (ref "U$3") (pin "S4") (pinfunction "52(SCK)_S4") (pintype "bidirectional"))
    )
    (net (code "51") (name "TRIGGER_PWM") (class "Default")
      (node (ref "R501") (pin "2") (pinfunction "2_2") (pintype "passive"))
    )
    (net (code "52") (name "TRIGGER_PWR_EN") (class "Default")
      (node (ref "R503") (pin "1") (pinfunction "1_1") (pintype "passive"))
    )
    (net (code "53") (name "TRIGGER_PWR_RTN") (class "Default")
      (node (ref "D501") (pin "A") (pinfunction "A_A") (pintype "passive"))
      (node (ref "D502") (pin "A") (pinfunction "A_A") (pintype "passive"))
      (node (ref "J606") (pin "1") (pinfunction "KL_1") (pintype "passive"))
      (node (ref "Q501") (pin "D") (pinfunction "D_D") (pintype "passive"))
    )
    (net (code "54") (name "TX+") (class "Default")
      (node (ref "IC402") (pin "6") (pinfunction "A_6") (pintype "passive"))
      (node (ref "J608") (pin "4") (pinfunction "4_4") (pintype "passive"))
      (node (ref "J609") (pin "4") (pinfunction "4_4") (pintype "passive"))
      (node (ref "R402") (pin "1") (pinfunction "1_1") (pintype "passive"))
    )
    (net (code "55") (name "TX-") (class "Default")
      (node (ref "IC402") (pin "7") (pinfunction "B_7") (pintype "passive"))
      (node (ref "J608") (pin "3") (pinfunction "3_3") (pintype "passive"))
      (node (ref "J609") (pin "3") (pinfunction "3_3") (pintype "passive"))
      (node (ref "R402") (pin "2") (pinfunction "2_2") (pintype "passive"))
    )
    (net (code "56") (name "TXCAN") (class "Default")
      (node (ref "IC403") (pin "1") (pinfunction "TXCAN_1") (pintype "bidirectional"))
      (node (ref "IC404") (pin "1") (pinfunction "TXD_1") (pintype "bidirectional"))
    )
    (net (code "57") (name "T_DOWN_LIM") (class "Default")
      (node (ref "J607") (pin "4") (pinfunction "4_4") (pintype "passive"))
      (node (ref "U$7") (pin "Z1") (pinfunction "37_Z1") (pintype "bidirectional"))
    )
    (net (code "58") (name "T_ENABLE") (class "Default")
      (node (ref "R603") (pin "2") (pinfunction "2_2") (pintype "passive"))
      (node (ref "U$9") (pin "Y5") (pinfunction "48_Y5") (pintype "bidirectional"))
    )
    (net (code "59") (name "T_FAULT_RESET") (class "Default")
      (node (ref "R604") (pin "2") (pinfunction "2_2") (pintype "passive"))
      (node (ref "U$9") (pin "Y3") (pinfunction "12*_Y3") (pintype "bidirectional"))
    )
    (net (code "60") (name "T_FEED1") (class "Default")
      (node (ref "IC301") (pin "5") (pinfunction "PD3(INT1)_5") (pintype "bidirectional"))
      (node (ref "J614") (pin "3") (pinfunction "3_3") (pintype "passive"))
      (node (ref "R616") (pin "1") (pinfunction "1_1") (pintype "passive"))
    )
    (net (code "61") (name "T_FEED2") (class "Default")
      (node (ref "IC301") (pin "26") (pinfunction "PC3(ADC3)_26") (pintype "bidirectional"))
      (node (ref "J614") (pin "2") (pinfunction "2_2") (pintype "passive"))
      (node (ref "R614") (pin "1") (pinfunction "1_1") (pintype "passive"))
    )
    (net (code "62") (name "T_FEED3") (class "Default")
      (node (ref "IC301") (pin "25") (pinfunction "PC2(ADC2)_25") (pintype "bidirectional"))
      (node (ref "J614") (pin "1") (pinfunction "1_1") (pintype "passive"))
      (node (ref "R612") (pin "1") (pinfunction "1_1") (pintype "passive"))
    )
    (net (code "63") (name "T_HALL1{slash}A") (class "Default")
      (node (ref "J615") (pin "3") (pinfunction "3_3") (pintype "passive"))
      (node (ref "R615") (pin "1") (pinfunction "1_1") (pintype "passive"))
      (node (ref "R616") (pin "2") (pinfunction "2_2") (pintype "passive"))
    )
    (net (code "64") (name "T_HALL2{slash}B") (class "Default")
      (node (ref "J615") (pin "4") (pinfunction "4_4") (pintype "passive"))
      (node (ref "R613") (pin "1") (pinfunction "1_1") (pintype "passive"))
      (node (ref "R614") (pin "2") (pinfunction "2_2") (pintype "passive"))
    )
    (net (code "65") (name "T_HALL3{slash}Z") (class "Default")
      (node (ref "J615") (pin "5") (pinfunction "5_5") (pintype "passive"))
      (node (ref "R611") (pin "1") (pinfunction "1_1") (pintype "passive"))
      (node (ref "R612") (pin "2") (pinfunction "2_2") (pintype "passive"))
    )
    (net (code "66") (name "T_HEALTH") (class "Default")
      (node (ref "D602") (pin "A") (pinfunction "A_A") (pintype "passive"))
      (node (ref "U$9") (pin "Y1") (pinfunction "10*_Y1") (pintype "bidirectional"))
    )
    (net (code "67") (name "T_UP_LIM") (class "Default")
      (node (ref "J607") (pin "3") (pinfunction "3_3") (pintype "passive"))
      (node (ref "U$7") (pin "Z3") (pinfunction "35_Z3") (pintype "bidirectional"))
    )
    (net (code "68") (name "T_VDD") (class "Default")
      (node (ref "J614") (pin "6") (pinfunction "6_6") (pintype "passive"))
      (node (ref "J615") (pin "6") (pinfunction "6_6") (pintype "passive"))
      (node (ref "R611") (pin "2") (pinfunction "2_2") (pintype "passive"))
      (node (ref "R613") (pin "2") (pinfunction "2_2") (pintype "passive"))
      (node (ref "R615") (pin "2") (pinfunction "2_2") (pintype "passive"))
    )
    (net (code "69") (name "V+") (class "Default")
      (node (ref "C601") (pin "+") (pinfunction "+_+") (pintype "passive"))
      (node (ref "C602") (pin "+") (pinfunction "+_+") (pintype "passive"))
      (node (ref "D201") (pin "C") (pinfunction "C_C") (pintype "passive"))
      (node (ref "D501") (pin "C") (pinfunction "C_C") (pintype "passive"))
      (node (ref "D502") (pin "C") (pinfunction "C_C") (pintype "passive"))
      (node (ref "IC501") (pin "4") (pinfunction "COL_4") (pintype "passive"))
      (node (ref "J601") (pin "1") (pinfunction "1_1") (pintype "passive"))
      (node (ref "J601") (pin "2") (pinfunction "2_2") (pintype "passive"))
      (node (ref "J603") (pin "6") (pinfunction "6_6") (pintype "passive"))
      (node (ref "J604") (pin "1") (pinfunction "KL_1") (pintype "passive"))
      (node (ref "J605") (pin "1") (pinfunction "KL_1") (pintype "passive"))
      (node (ref "J606") (pin "2") (pinfunction "KL_2") (pintype "passive"))
      (node (ref "U201") (pin "1") (pinfunction "IN+_1") (pintype "input"))
    )
    (net (code "70") (name "V-") (class "Default")
      (node (ref "C601") (pin "-") (pinfunction "-_-") (pintype "passive"))
      (node (ref "C602") (pin "-") (pinfunction "-_-") (pintype "passive"))
      (node (ref "D201") (pin "A") (pinfunction "A_A") (pintype "passive"))
      (node (ref "J601") (pin "3") (pinfunction "3_3") (pintype "passive"))
      (node (ref "J601") (pin "4") (pinfunction "4_4") (pintype "passive"))
      (node (ref "J603") (pin "5") (pinfunction "5_5") (pintype "passive"))
      (node (ref "J604") (pin "2") (pinfunction "KL_2") (pintype "passive"))
      (node (ref "J605") (pin "2") (pinfunction "KL_2") (pintype "passive"))
      (node (ref "Q501") (pin "S") (pinfunction "S_S") (pintype "passive"))
      (node (ref "R502") (pin "1") (pinfunction "1_1") (pintype "passive"))
      (node (ref "SJ201") (pin "1") (pinfunction "1_1") (pintype "passive"))
      (node (ref "SJ202") (pin "1") (pinfunction "1_1") (pintype "passive"))
      (node (ref "SJ203") (pin "1") (pinfunction "1_1") (pintype "passive"))
      (node (ref "SJ204") (pin "1") (pinfunction "1_1") (pintype "passive"))
      (node (ref "U201") (pin "2") (pinfunction "IN-_2") (pintype "passive"))
    )
    (net (code "71") (name "VCC") (class "Default")
      (node (ref "C203") (pin "+") (pinfunction "+_+") (pintype "passive"))
      (node (ref "C204") (pin "1") (pinfunction "1_1") (pintype "passive"))
      (node (ref "C305") (pin "1") (pinfunction "1_1") (pintype "passive"))
      (node (ref "C402") (pin "1") (pinfunction "1_1") (pintype "passive"))
      (node (ref "D101") (pin "C") (pinfunction "C_C") (pintype "passive"))
      (node (ref "D301") (pin "C") (pinfunction "C_C") (pintype "passive"))
      (node (ref "D401") (pin "C") (pinfunction "C_C") (pintype "passive"))
      (node (ref "IC301") (pin "20") (pinfunction "AVCC_20") (pintype "bidirectional"))
      (node (ref "IC301") (pin "7") (pinfunction "VCC_7") (pintype "bidirectional"))
      (node (ref "IC401") (pin "2") (pinfunction "RE/_2") (pintype "input"))
      (node (ref "IC401") (pin "3") (pinfunction "DE_3") (pintype "input"))
      (node (ref "IC403") (pin "18") (pinfunction "VDD_18") (pintype "bidirectional"))
      (node (ref "IC404") (pin "3") (pinfunction "VCC_3") (pintype "bidirectional"))
      (node (ref "R301") (pin "2") (pinfunction "2_2") (pintype "passive"))
      (node (ref "R404") (pin "1") (pinfunction "1_1") (pintype "passive"))
      (node (ref "R405") (pin "2") (pinfunction "2_2") (pintype "passive"))
      (node (ref "U101") (pin "P5") (pinfunction "5V_P5") (pintype "bidirectional"))
      (node (ref "U201") (pin "3") (pinfunction "OUT+_3") (pintype "passive"))
    )
    (net (code "72") (name "VIDEO+") (class "Default")
      (node (ref "J602") (pin "3") (pinfunction "3_3") (pintype "passive"))
      (node (ref "J603") (pin "2") (pinfunction "2_2") (pintype "passive"))
    )
    (net (code "73") (name "VIDEO-") (class "Default")
      (node (ref "J602") (pin "4") (pinfunction "4_4") (pintype "passive"))
      (node (ref "J603") (pin "1") (pinfunction "1_1") (pintype "passive"))
    )
    (net (code "74") (name "unconnected-(IC301-PB0(ICP)-Pad14)") (class "Default")
      (node (ref "IC301") (pin "14") (pinfunction "PB0(ICP)_14") (pintype "bidirectional"))
    )
    (net (code "75") (name "unconnected-(IC301-PB1(OC1A)-Pad15)") (class "Default")
      (node (ref "IC301") (pin "15") (pinfunction "PB1(OC1A)_15") (pintype "bidirectional"))
    )
    (net (code "76") (name "unconnected-(IC301-PB2(SS{slash}OC1B)-Pad16)") (class "Default")
      (node (ref "IC301") (pin "16") (pinfunction "PB2(SS/OC1B)_16") (pintype "bidirectional"))
    )
    (net (code "77") (name "unconnected-(IC301-PB3(MOSI{slash}OC2)-Pad17)") (class "Default")
      (node (ref "IC301") (pin "17") (pinfunction "PB3(MOSI/OC2)_17") (pintype "bidirectional"))
    )
    (net (code "78") (name "unconnected-(IC301-PB4(MISO)-Pad18)") (class "Default")
      (node (ref "IC301") (pin "18") (pinfunction "PB4(MISO)_18") (pintype "bidirectional"))
    )
    (net (code "79") (name "unconnected-(IC301-PB5(SCK)-Pad19)") (class "Default")
      (node (ref "IC301") (pin "19") (pinfunction "PB5(SCK)_19") (pintype "bidirectional"))
    )
    (net (code "80") (name "unconnected-(IC301-PC0(ADC0)-Pad23)") (class "Default")
      (node (ref "IC301") (pin "23") (pinfunction "PC0(ADC0)_23") (pintype "bidirectional"))
    )
    (net (code "81") (name "unconnected-(IC301-PC1(ADC1)-Pad24)") (class "Default")
      (node (ref "IC301") (pin "24") (pinfunction "PC1(ADC1)_24") (pintype "bidirectional"))
    )
    (net (code "82") (name "unconnected-(IC301-PD4(XCK{slash}T0)-Pad6)") (class "Default")
      (node (ref "IC301") (pin "6") (pinfunction "PD4(XCK/T0)_6") (pintype "bidirectional"))
    )
    (net (code "83") (name "unconnected-(IC301-PD5(T1)-Pad11)") (class "Default")
      (node (ref "IC301") (pin "11") (pinfunction "PD5(T1)_11") (pintype "bidirectional"))
    )
    (net (code "84") (name "unconnected-(IC301-PD6(AIN0)-Pad12)") (class "Default")
      (node (ref "IC301") (pin "12") (pinfunction "PD6(AIN0)_12") (pintype "bidirectional"))
    )
    (net (code "85") (name "unconnected-(IC301-PD7(AIN1)-Pad13)") (class "Default")
      (node (ref "IC301") (pin "13") (pinfunction "PD7(AIN1)_13") (pintype "bidirectional"))
    )
    (net (code "86") (name "unconnected-(IC401A-RO-Pad1)") (class "Default")
      (node (ref "IC401") (pin "1") (pinfunction "RO_1") (pintype "output"))
    )
    (net (code "87") (name "unconnected-(IC402A-DI-Pad4)") (class "Default")
      (node (ref "IC402") (pin "4") (pinfunction "DI_4") (pintype "input"))
    )
    (net (code "88") (name "unconnected-(IC403-CLKOUT{slash}SOF-Pad3)") (class "Default")
      (node (ref "IC403") (pin "3") (pinfunction "CLKOUT/SOF_3") (pintype "bidirectional"))
    )
    (net (code "89") (name "unconnected-(IC403-~{RX0BF}-Pad11)") (class "Default")
      (node (ref "IC403") (pin "11") (pinfunction "~{RX0BF}_11") (pintype "bidirectional"))
    )
    (net (code "90") (name "unconnected-(IC403-~{RX1BF}-Pad10)") (class "Default")
      (node (ref "IC403") (pin "10") (pinfunction "~{RX1BF}_10") (pintype "bidirectional"))
    )
    (net (code "91") (name "unconnected-(IC403-~{TX0RTS}-Pad4)") (class "Default")
      (node (ref "IC403") (pin "4") (pinfunction "~{TX0RTS}_4") (pintype "bidirectional"))
    )
    (net (code "92") (name "unconnected-(IC403-~{TX1RTS}-Pad5)") (class "Default")
      (node (ref "IC403") (pin "5") (pinfunction "~{TX1RTS}_5") (pintype "bidirectional"))
    )
    (net (code "93") (name "unconnected-(IC403-~{TX2RTS}-Pad6)") (class "Default")
      (node (ref "IC403") (pin "6") (pinfunction "~{TX2RTS}_6") (pintype "bidirectional"))
    )
    (net (code "94") (name "unconnected-(IC404-SPLIT-Pad5)") (class "Default")
      (node (ref "IC404") (pin "5") (pinfunction "SPLIT_5") (pintype "bidirectional"))
    )
    (net (code "95") (name "unconnected-(U$3-5V-PadS5)") (class "Default")
      (node (ref "U$3") (pin "S5") (pinfunction "5V_S5") (pintype "bidirectional"))
    )
    (net (code "96") (name "unconnected-(U$3-GND-PadS1)") (class "Default")
      (node (ref "U$3") (pin "S1") (pinfunction "GND_S1") (pintype "bidirectional"))
    )
    (net (code "97") (name "unconnected-(U$3-~{RESET}-PadS2)") (class "Default")
      (node (ref "U$3") (pin "S2") (pinfunction "~{RESET}_S2") (pintype "bidirectional"))
    )
    (net (code "98") (name "unconnected-(U101-3V3-PadP1)") (class "Default")
      (node (ref "U101") (pin "P1") (pinfunction "3V3_P1") (pintype "bidirectional"))
    )
    (net (code "99") (name "~{RESET1}") (class "Default")
      (node (ref "C301") (pin "1") (pinfunction "1_1") (pintype "passive"))
      (node (ref "D301") (pin "A") (pinfunction "A_A") (pintype "passive"))
      (node (ref "IC301") (pin "1") (pinfunction "PC6(/RESET)_1") (pintype "bidirectional"))
      (node (ref "R301") (pin "1") (pinfunction "1_1") (pintype "passive"))
    )
  )
)
